# USB.net
KiCad netlist of a schematic drawn in Altium Designer
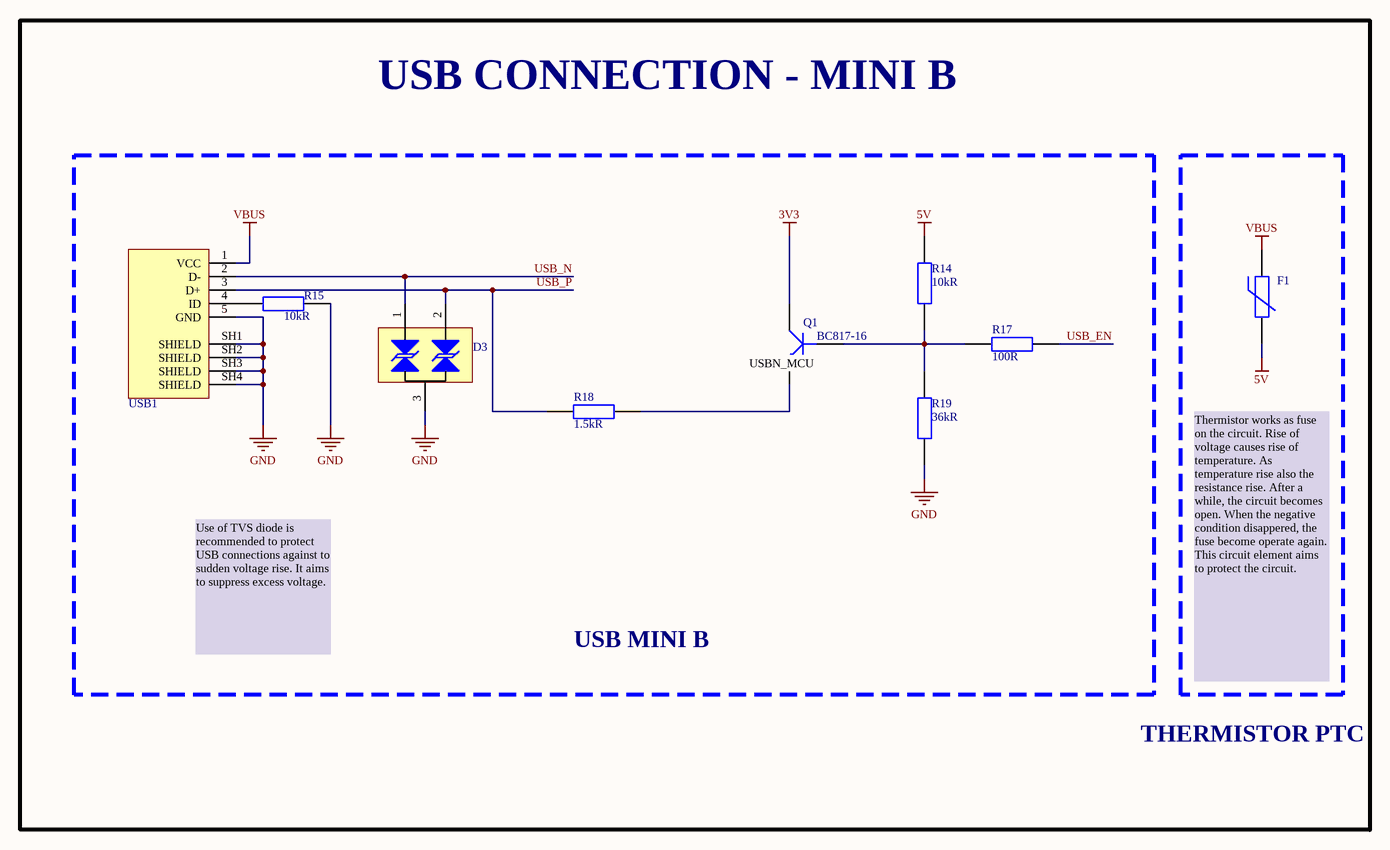
[diagram p0: USB.SchDoc]

(export (version "E")
  (design (tool "Eeschema 10.0.6"))
  (components
    (comp (ref "D3")
      (value "SM712")
      (footprint "SOT-23")
      (description "7V/12V Tvs, Package SOT-23, Tvs A")
      (fields
        (field (name "MANUFACTURER") "Sangdest Microelectronics")
        (field (name "DESIGNEDBY") "Aslı Kurt")
      )
      (libsource (lib "MyLibrary") (part "SM712"))
    )
    (comp (ref "F1")
      (value "PRG21BC1R0MM1RA")
      (footprint "FUSE_0805")
      (description "Thermistor PTC 1 Ohm 20% 2-Pin 0805 Surface Mount Solder Pad Embossed T/R")
      (fields (field (name "MANUFACTURER") "Murata") (field (name "DESIGNEDBY") "Aslı Kurt"))
      (libsource (lib "MyLibrary") (part "PRG21BC1R0MM1RA"))
    )
    (comp (ref "Q1")
      (value "BC817-16")
      (footprint "SOT23")
      (description "ON Semi BC817-16LT1G NPN Bipolar Transistor; 0.5 A; 45 V; 3-Pin SOT-23")
      (fields
        (field (name "MANUFACTURER") "ON Semiconductor")
        (field (name "MANUFACTURER PART NUMBER") "BC817-16LT1G")
        (field (name "DESIGNEDBY") "Aslı Kurt")
      )
      (libsource (lib "MyLibrary") (part "BC817-16"))
    )
    (comp (ref "R14")
      (value "RC0603FR-0710KL")
      (footprint "RES_0603")
      (description "RES 10K %1 OHM 0603 SMD")
      (fields
        (field (name "MANUFACTURER") "Yageo")
        (field (name "TOLERANCE") "1%")
        (field (name "RESISTANCE") "10kR")
        (field (name "DESIGNEDBY") "Aslı Kurt")
      )
      (libsource (lib "MyLibrary") (part "RES 10K OHM 0603"))
    )
    (comp (ref "R15")
      (value "RC0603FR-0710KL")
      (footprint "RES_0603")
      (description "RES 10K %1 OHM 0603 SMD")
      (fields
        (field (name "MANUFACTURER") "Yageo")
        (field (name "TOLERANCE") "1%")
        (field (name "RESISTANCE") "10kR")
        (field (name "DESIGNEDBY") "Aslı Kurt")
      )
      (libsource (lib "") (part "RES 10K OHM 0603_1"))
    )
    (comp (ref "R17")
      (value "RC0603JR-07100RL")
      (footprint "RES_0603")
      (description "RES 100 %5 OHM 0603 SMD")
      (fields
        (field (name "MANUFACTURER") "Yageo")
        (field (name "TOLERANCE") "5%")
        (field (name "RESISTANCE") "100R")
        (field (name "DESIGNEDBY") "Aslı Kurt")
      )
      (libsource (lib "MyLibrary") (part "RES 100 OHM 0603"))
    )
    (comp (ref "R18")
      (value "RC0805FR-071K5L")
      (footprint "RES_0805")
      (description "SMD Chip Resistor, 1.5 kOhm, ï¿½ 1%, 125 mW, 0805 [2012 Metric], Thick Film, General Purpose")
      (fields
        (field (name "MANUFACTURER") "Yageo")
        (field (name "TOLERANCE") "1%")
        (field (name "RESISTANCE") "1.5kR")
        (field (name "DESIGNEDBY") "Aslı Kurt")
      )
      (libsource (lib "MyLibrary") (part "RES 1K5 OHM 0805"))
    )
    (comp (ref "R19")
      (value "RC0805FR-0736KL")
      (footprint "RES_0805")
      (description "SMD Chip Resistor, 36 kOhm, ± 1%, 125 mW, 0805 [2012 Metric], Thick Film, General Purpose")
      (fields
        (field (name "MANUFACTURER") "Yageo")
        (field (name "TOLERANCE") "1%")
        (field (name "RESISTANCE") "36kR")
        (field (name "DESIGNEDBY") "Aslı Kurt")
      )
      (libsource (lib "MyLibrary") (part "RES 36K OHM 0805"))
    )
    (comp (ref "USB1")
      (value "690-005-299-043")
      (footprint "MINI_USB_B")
      (description "Conn Mini USB 2.0 Type B RCP 5 POS 0.8mm Solder RA SMD 5 Terminal 1 Port")
      (fields (field (name "MANUFACTURER") "EDAC") (field (name "DESIGNEDBY") "Aslı Kurt"))
      (libsource (lib "MyLibrary") (part "690-005-299-043"))
    )
  )
  (nets
    (net (code "1") (name "/USB_EN") (class "Default")
      (node (ref "R17") (pin "2") (pinfunction "2_2") (pintype "passive"))
    )
    (net (code "2") (name "/USB_N") (class "Default")
      (node (ref "D3") (pin "1") (pinfunction "1_1") (pintype "passive"))
      (node (ref "USB1") (pin "2") (pinfunction "D-_2") (pintype "passive"))
    )
    (net (code "3") (name "/USB_P") (class "Default")
      (node (ref "D3") (pin "2") (pinfunction "2_2") (pintype "passive"))
      (node (ref "R18") (pin "1") (pinfunction "1_1") (pintype "passive"))
      (node (ref "USB1") (pin "3") (pinfunction "D+_3") (pintype "passive"))
    )
    (net (code "4") (name "3V3") (class "Default")
      (node (ref "Q1") (pin "1") (pinfunction "C_1") (pintype "power_in"))
    )
    (net (code "5") (name "5V") (class "Default")
      (node (ref "F1") (pin "2") (pinfunction "2_2") (pintype "passive"))
      (node (ref "R14") (pin "2") (pinfunction "2_2") (pintype "passive"))
    )
    (net (code "6") (name "GND") (class "Default")
      (node (ref "D3") (pin "3") (pinfunction "3_3") (pintype "passive"))
      (node (ref "R15") (pin "2") (pinfunction "2_2") (pintype "passive"))
      (node (ref "R19") (pin "1") (pinfunction "1_1") (pintype "passive"))
      (node (ref "USB1") (pin "5") (pinfunction "GND_5") (pintype "passive"))
      (node (ref "USB1") (pin "SH1") (pinfunction "SHIELD_SH1") (pintype "passive"))
      (node (ref "USB1") (pin "SH2") (pinfunction "SHIELD_SH2") (pintype "passive"))
      (node (ref "USB1") (pin "SH3") (pinfunction "SHIELD_SH3") (pintype "passive"))
      (node (ref "USB1") (pin "SH4") (pinfunction "SHIELD_SH4") (pintype "passive"))
    )
    (net (code "7") (name "Net-(Q1-B)") (class "Default")
      (node (ref "Q1") (pin "2") (pinfunction "B_2") (pintype "power_in"))
      (node (ref "R14") (pin "1") (pinfunction "1_1") (pintype "passive"))
      (node (ref "R17") (pin "1") (pinfunction "1_1") (pintype "passive"))
      (node (ref "R19") (pin "2") (pinfunction "2_2") (pintype "passive"))
    )
    (net (code "8") (name "Net-(Q1-E)") (class "Default")
      (node (ref "Q1") (pin "3") (pinfunction "E_3") (pintype "power_in"))
      (node (ref "R18") (pin "2") (pinfunction "2_2") (pintype "passive"))
    )
    (net (code "9") (name "Net-(USB1-ID)") (class "Default")
      (node (ref "R15") (pin "1") (pinfunction "1_1") (pintype "passive"))
      (node (ref "USB1") (pin "4") (pinfunction "ID_4") (pintype "passive"))
    )
    (net (code "10") (name "VBUS") (class "Default")
      (node (ref "F1") (pin "1") (pinfunction "1_1") (pintype "passive"))
      (node (ref "USB1") (pin "1") (pinfunction "VCC_1") (pintype "passive"))
    )
  )
)
